# analog_sensor_single_channel_R1.net
KiCad netlist of a schematic drawn in EAGLE
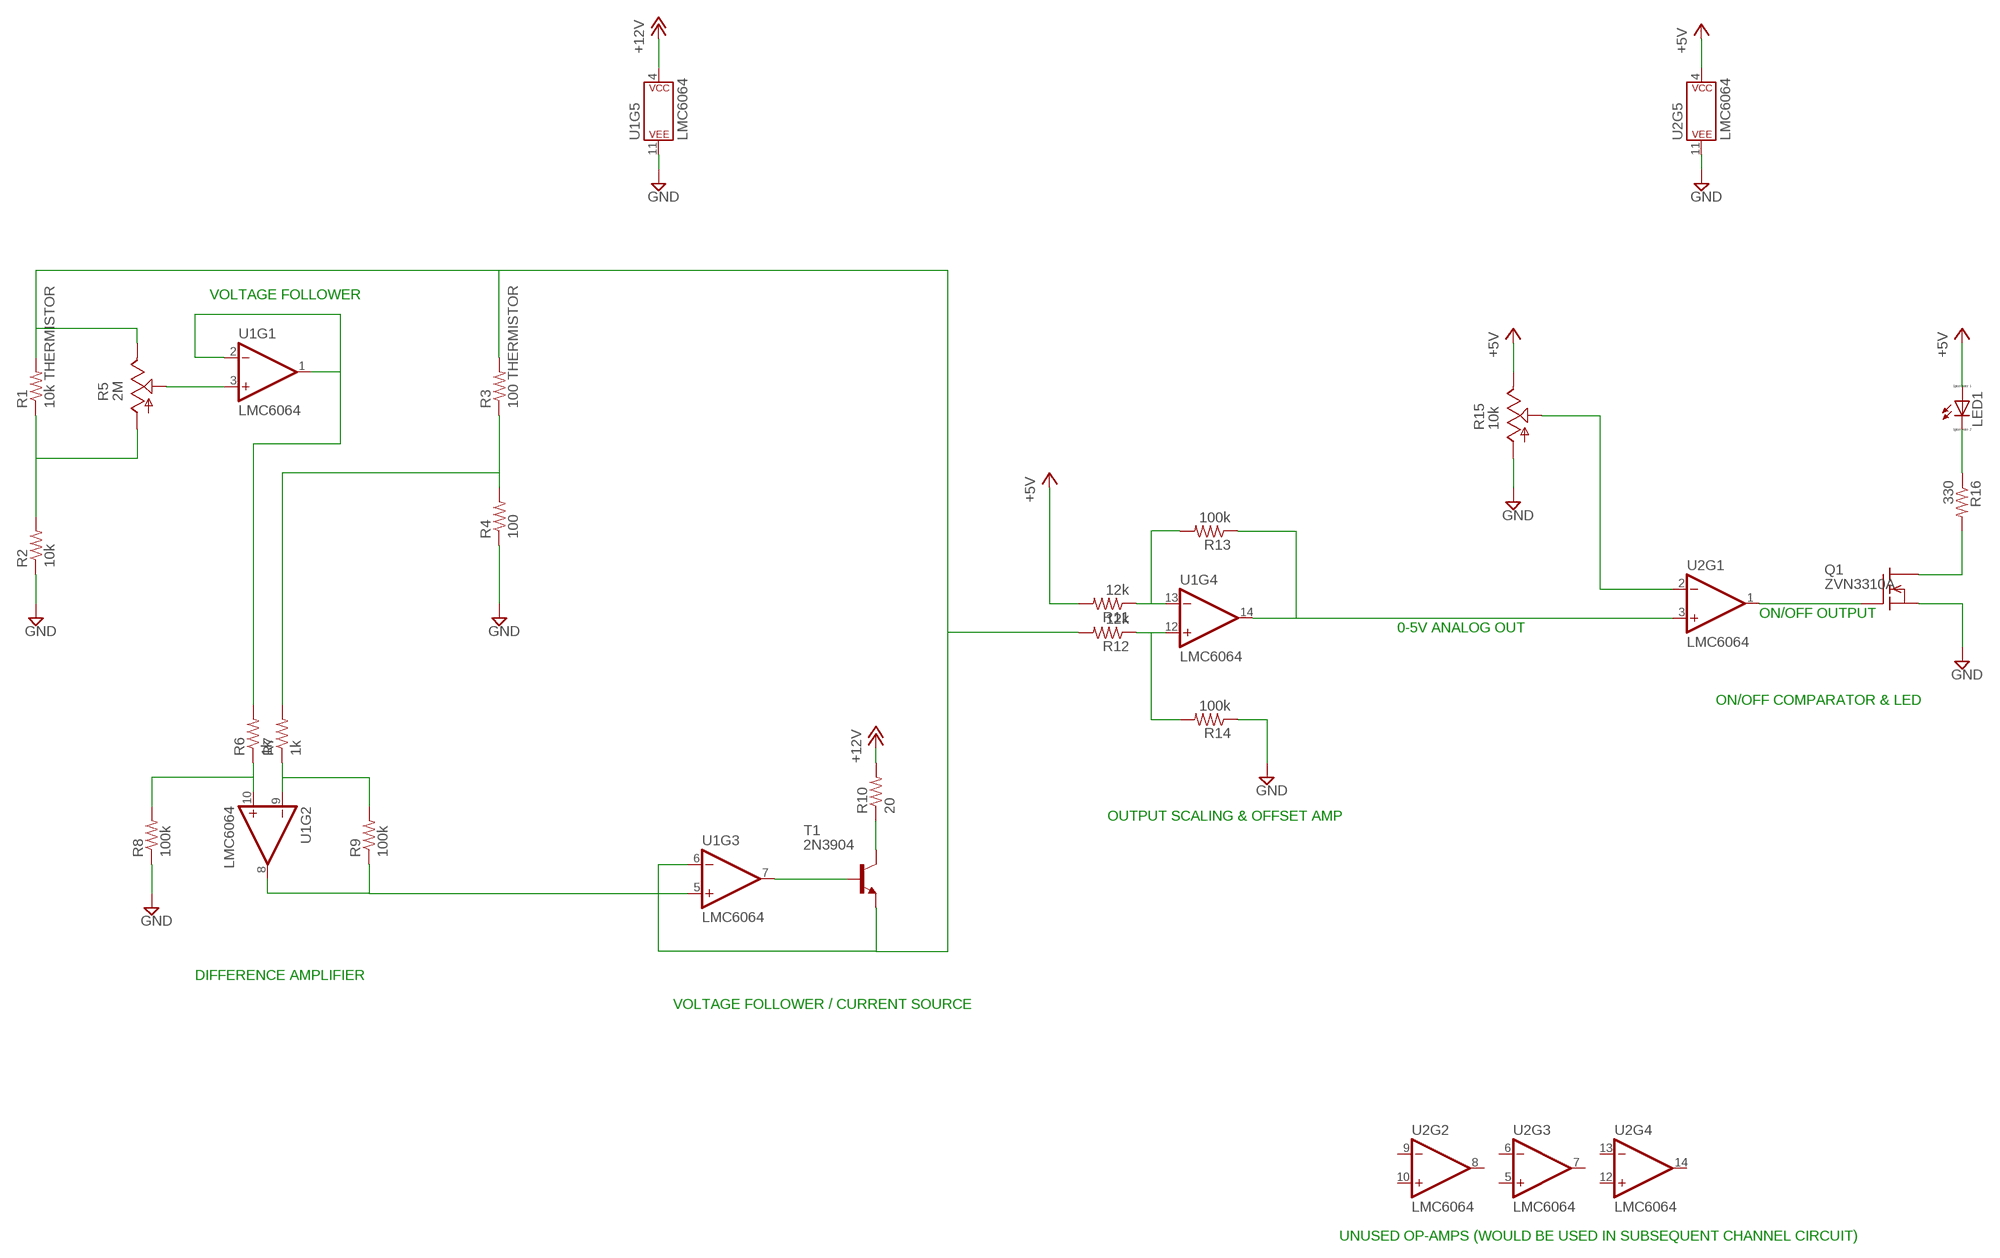
[diagram p0: schematic, sheet 1]

(export (version "E")
  (design (tool "Eeschema 10.0.6"))
  (components
    (comp (ref "LED1")
      (value "LED_E")
      (footprint "eagle-import:LED_1206")
      (libsource (lib "eagle-import") (part "LED_E"))
    )
    (comp (ref "Q1")
      (value "ZVN3310A")
      (footprint "eagle-import:TO92")
      (libsource (lib "eagle-import") (part "ZVN3310A"))
    )
    (comp (ref "R1")
      (value "10k THERMISTOR")
      (footprint "eagle-import:R0603")
      (libsource (lib "eagle-import") (part "R-US_R0603"))
    )
    (comp (ref "R2")
      (value "10k")
      (footprint "eagle-import:R0603")
      (libsource (lib "eagle-import") (part "R-US_R0603"))
    )
    (comp (ref "R3")
      (value "100 THERMISTOR")
      (footprint "eagle-import:R0603")
      (libsource (lib "eagle-import") (part "R-US_R0603"))
    )
    (comp (ref "R4")
      (value "100")
      (footprint "eagle-import:R0603")
      (libsource (lib "eagle-import") (part "R-US_R0603"))
    )
    (comp (ref "R5")
      (value "2M")
      (footprint "eagle-import:SM-42_43W")
      (libsource (lib "eagle-import") (part "TRIM_US-SM-42/43W"))
    )
    (comp (ref "R6")
      (value "1k")
      (footprint "eagle-import:R0603")
      (libsource (lib "eagle-import") (part "R-US_R0603"))
    )
    (comp (ref "R7")
      (value "1k")
      (footprint "eagle-import:R0603")
      (libsource (lib "eagle-import") (part "R-US_R0603"))
    )
    (comp (ref "R8")
      (value "100k")
      (footprint "eagle-import:R0603")
      (libsource (lib "eagle-import") (part "R-US_R0603"))
    )
    (comp (ref "R9")
      (value "100k")
      (footprint "eagle-import:R0603")
      (libsource (lib "eagle-import") (part "R-US_R0603"))
    )
    (comp (ref "R10")
      (value "20")
      (footprint "eagle-import:R0603")
      (libsource (lib "eagle-import") (part "R-US_R0603"))
    )
    (comp (ref "R11")
      (value "12k")
      (footprint "eagle-import:R0603")
      (libsource (lib "eagle-import") (part "R-US_R0603"))
    )
    (comp (ref "R12")
      (value "12k")
      (footprint "eagle-import:R0603")
      (libsource (lib "eagle-import") (part "R-US_R0603"))
    )
    (comp (ref "R13")
      (value "100k")
      (footprint "eagle-import:R0603")
      (libsource (lib "eagle-import") (part "R-US_R0603"))
    )
    (comp (ref "R14")
      (value "100k")
      (footprint "eagle-import:R0603")
      (libsource (lib "eagle-import") (part "R-US_R0603"))
    )
    (comp (ref "R15")
      (value "10k")
      (footprint "eagle-import:SM-42_43W")
      (libsource (lib "eagle-import") (part "TRIM_US-SM-42/43W"))
    )
    (comp (ref "R16")
      (value "330")
      (footprint "eagle-import:R0603")
      (libsource (lib "eagle-import") (part "R-US_R0603"))
    )
    (comp (ref "T1")
      (value "2N3904")
      (footprint "eagle-import:TO92")
      (libsource (lib "eagle-import") (part "2N3904"))
    )
    (comp (ref "U1")
      (value "LMC6064")
      (footprint "eagle-import:SO14")
      (libsource (lib "eagle-import") (part "LMC6064"))
    )
    (comp (ref "U2")
      (value "LMC6064")
      (footprint "eagle-import:SO14")
      (libsource (lib "eagle-import") (part "LMC6064"))
    )
  )
  (nets
    (net (code "1") (name "+5V") (class "Default")
      (node (ref "LED1") (pin "A") (pinfunction "A_A") (pintype "passive"))
      (node (ref "R11") (pin "2") (pinfunction "2_2") (pintype "passive"))
      (node (ref "R15") (pin "3") (pinfunction "E_3") (pintype "passive"))
      (node (ref "U2") (pin "4") (pinfunction "P$V+_4") (pintype "bidirectional"))
    )
    (net (code "2") (name "+12V") (class "Default")
      (node (ref "R10") (pin "2") (pinfunction "2_2") (pintype "passive"))
      (node (ref "U1") (pin "4") (pinfunction "P$V+_4") (pintype "bidirectional"))
    )
    (net (code "3") (name "GND") (class "Default")
      (node (ref "Q1") (pin "3") (pinfunction "S_3") (pintype "passive"))
      (node (ref "R14") (pin "1") (pinfunction "1_1") (pintype "passive"))
      (node (ref "R15") (pin "1") (pinfunction "A_1") (pintype "passive"))
      (node (ref "R2") (pin "1") (pinfunction "1_1") (pintype "passive"))
      (node (ref "R4") (pin "1") (pinfunction "1_1") (pintype "passive"))
      (node (ref "R8") (pin "1") (pinfunction "1_1") (pintype "passive"))
      (node (ref "U1") (pin "11") (pinfunction "P$V-_11") (pintype "bidirectional"))
      (node (ref "U2") (pin "11") (pinfunction "P$V-_11") (pintype "bidirectional"))
    )
    (net (code "4") (name "Net-(LED1-PadC)") (class "Default")
      (node (ref "LED1") (pin "C") (pinfunction "C_C") (pintype "passive"))
      (node (ref "R16") (pin "1") (pinfunction "1_1") (pintype "passive"))
    )
    (net (code "5") (name "Net-(Q1-D)") (class "Default")
      (node (ref "Q1") (pin "2") (pinfunction "D_2") (pintype "passive"))
      (node (ref "R16") (pin "2") (pinfunction "2_2") (pintype "passive"))
    )
    (net (code "6") (name "Net-(Q1-G)") (class "Default")
      (node (ref "Q1") (pin "1") (pinfunction "G_1") (pintype "passive"))
      (node (ref "U2") (pin "1") (pinfunction "OUT_1") (pintype "output"))
    )
    (net (code "7") (name "Net-(R3-Pad1)") (class "Default")
      (node (ref "R3") (pin "1") (pinfunction "1_1") (pintype "passive"))
      (node (ref "R4") (pin "2") (pinfunction "2_2") (pintype "passive"))
      (node (ref "R7") (pin "2") (pinfunction "2_2") (pintype "passive"))
    )
    (net (code "8") (name "Net-(R5-A)") (class "Default")
      (node (ref "R1") (pin "1") (pinfunction "1_1") (pintype "passive"))
      (node (ref "R2") (pin "2") (pinfunction "2_2") (pintype "passive"))
      (node (ref "R5") (pin "1") (pinfunction "A_1") (pintype "passive"))
    )
    (net (code "9") (name "Net-(R5-E)") (class "Default")
      (node (ref "R1") (pin "2") (pinfunction "2_2") (pintype "passive"))
      (node (ref "R12") (pin "2") (pinfunction "2_2") (pintype "passive"))
      (node (ref "R3") (pin "2") (pinfunction "2_2") (pintype "passive"))
      (node (ref "R5") (pin "3") (pinfunction "E_3") (pintype "passive"))
      (node (ref "T1") (pin "3") (pinfunction "E_3") (pintype "passive"))
      (node (ref "U1") (pin "6") (pinfunction "-IN_6") (pintype "input"))
    )
    (net (code "10") (name "Net-(R5-S)") (class "Default")
      (node (ref "R5") (pin "2") (pinfunction "S_2") (pintype "passive"))
      (node (ref "U1") (pin "3") (pinfunction "+IN_3") (pintype "input"))
    )
    (net (code "11") (name "Net-(R15-S)") (class "Default")
      (node (ref "R15") (pin "2") (pinfunction "S_2") (pintype "passive"))
      (node (ref "U2") (pin "2") (pinfunction "-IN_2") (pintype "input"))
    )
    (net (code "12") (name "Net-(T1-B)") (class "Default")
      (node (ref "T1") (pin "2") (pinfunction "B_2") (pintype "passive"))
      (node (ref "U1") (pin "7") (pinfunction "OUT_7") (pintype "output"))
    )
    (net (code "13") (name "Net-(T1-C)") (class "Default")
      (node (ref "R10") (pin "1") (pinfunction "1_1") (pintype "passive"))
      (node (ref "T1") (pin "1") (pinfunction "C_1") (pintype "passive"))
    )
    (net (code "14") (name "Net-(U1A--IN)") (class "Default")
      (node (ref "R6") (pin "2") (pinfunction "2_2") (pintype "passive"))
      (node (ref "U1") (pin "1") (pinfunction "OUT_1") (pintype "output"))
      (node (ref "U1") (pin "2") (pinfunction "-IN_2") (pintype "input"))
    )
    (net (code "15") (name "Net-(U1B-+IN)") (class "Default")
      (node (ref "R6") (pin "1") (pinfunction "1_1") (pintype "passive"))
      (node (ref "R8") (pin "2") (pinfunction "2_2") (pintype "passive"))
      (node (ref "U1") (pin "10") (pinfunction "+IN_10") (pintype "input"))
    )
    (net (code "16") (name "Net-(U1B--IN)") (class "Default")
      (node (ref "R7") (pin "1") (pinfunction "1_1") (pintype "passive"))
      (node (ref "R9") (pin "2") (pinfunction "2_2") (pintype "passive"))
      (node (ref "U1") (pin "9") (pinfunction "-IN_9") (pintype "input"))
    )
    (net (code "17") (name "Net-(U1B-OUT)") (class "Default")
      (node (ref "R9") (pin "1") (pinfunction "1_1") (pintype "passive"))
      (node (ref "U1") (pin "5") (pinfunction "+IN_5") (pintype "input"))
      (node (ref "U1") (pin "8") (pinfunction "OUT_8") (pintype "output"))
    )
    (net (code "18") (name "Net-(U1D-+IN)") (class "Default")
      (node (ref "R12") (pin "1") (pinfunction "1_1") (pintype "passive"))
      (node (ref "R14") (pin "2") (pinfunction "2_2") (pintype "passive"))
      (node (ref "U1") (pin "12") (pinfunction "+IN_12") (pintype "input"))
    )
    (net (code "19") (name "Net-(U1D--IN)") (class "Default")
      (node (ref "R11") (pin "1") (pinfunction "1_1") (pintype "passive"))
      (node (ref "R13") (pin "2") (pinfunction "2_2") (pintype "passive"))
      (node (ref "U1") (pin "13") (pinfunction "-IN_13") (pintype "input"))
    )
    (net (code "20") (name "Net-(U1D-OUT)") (class "Default")
      (node (ref "R13") (pin "1") (pinfunction "1_1") (pintype "passive"))
      (node (ref "U1") (pin "14") (pinfunction "OUT_14") (pintype "output"))
      (node (ref "U2") (pin "3") (pinfunction "+IN_3") (pintype "input"))
    )
    (net (code "21") (name "unconnected-(U2B-+IN-Pad10)") (class "Default")
      (node (ref "U2") (pin "10") (pinfunction "+IN_10") (pintype "input"))
    )
    (net (code "22") (name "unconnected-(U2B--IN-Pad9)") (class "Default")
      (node (ref "U2") (pin "9") (pinfunction "-IN_9") (pintype "input"))
    )
    (net (code "23") (name "unconnected-(U2B-OUT-Pad8)") (class "Default")
      (node (ref "U2") (pin "8") (pinfunction "OUT_8") (pintype "output"))
    )
    (net (code "24") (name "unconnected-(U2C-+IN-Pad5)") (class "Default")
      (node (ref "U2") (pin "5") (pinfunction "+IN_5") (pintype "input"))
    )
    (net (code "25") (name "unconnected-(U2C--IN-Pad6)") (class "Default")
      (node (ref "U2") (pin "6") (pinfunction "-IN_6") (pintype "input"))
    )
    (net (code "26") (name "unconnected-(U2C-OUT-Pad7)") (class "Default")
      (node (ref "U2") (pin "7") (pinfunction "OUT_7") (pintype "output"))
    )
    (net (code "27") (name "unconnected-(U2D-+IN-Pad12)") (class "Default")
      (node (ref "U2") (pin "12") (pinfunction "+IN_12") (pintype "input"))
    )
    (net (code "28") (name "unconnected-(U2D--IN-Pad13)") (class "Default")
      (node (ref "U2") (pin "13") (pinfunction "-IN_13") (pintype "input"))
    )
    (net (code "29") (name "unconnected-(U2D-OUT-Pad14)") (class "Default")
      (node (ref "U2") (pin "14") (pinfunction "OUT_14") (pintype "output"))
    )
  )
)
